# Acionamentos_valvula.net
KiCad netlist of a schematic drawn in Altium Designer
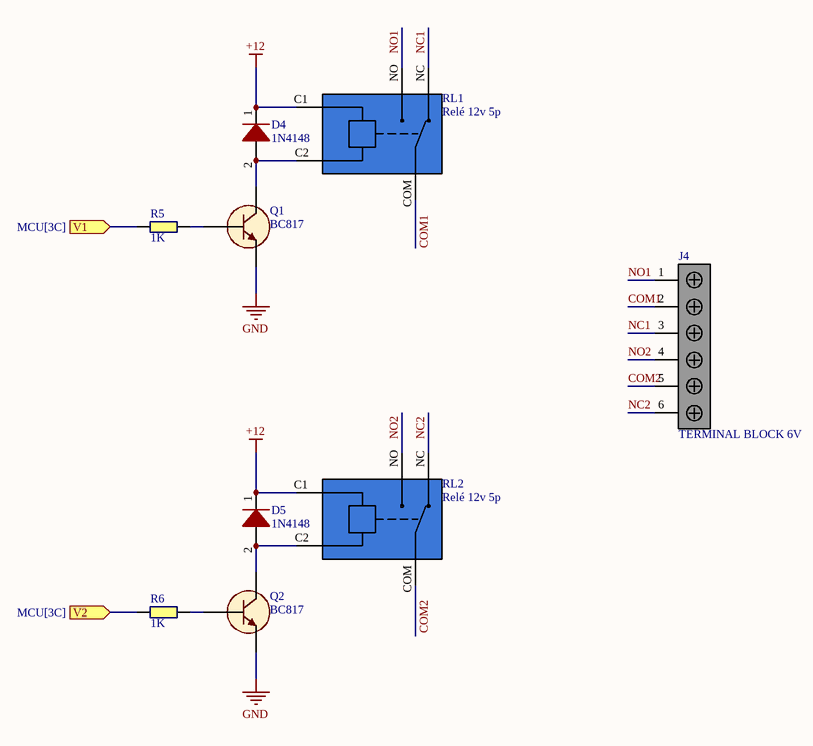
[diagram p0: Acionamentos valvula.SchDoc]

(export (version "E")
  (design (tool "Eeschema 10.0.6"))
  (components
    (comp (ref "D4")
      (value "1N4148")
      (footprint "DIOMELF3516N")
      (description "Diodo rapido")
      (fields (field (name "PUBLISHER") "Altium Limited"))
      (libsource (lib "Gerenciador de abastecimento") (part "DIODO 1N4148"))
    )
    (comp (ref "D5")
      (value "1N4148")
      (footprint "DIOMELF3516N")
      (description "Diodo rapido")
      (fields (field (name "PUBLISHER") "Altium Limited"))
      (libsource (lib "Gerenciador de abastecimento") (part "DIODO 1N4148"))
    )
    (comp (ref "J4")
      (value "TERMINAL BLOCK 6V")
      (footprint "Terminal block 5mm 6V")
      (description "Block, Terminal; 6 A; 63 V; 5 mm; 26 to 20 AWG; 6 Screw; Soldering; 1.5 kV")
      (libsource (lib "Gerenciador de abastecimento") (part "TERMINAL BLOCK 6V"))
    )
    (comp (ref "Q1")
      (value "BC817")
      (footprint "SOT23")
      (libsource (lib "Gerenciador de abastecimento") (part "BC817"))
    )
    (comp (ref "Q2")
      (value "BC817")
      (footprint "SOT23")
      (libsource (lib "Gerenciador de abastecimento") (part "BC817"))
    )
    (comp (ref "R5")
      (value "1K")
      (footprint "RESISTOR 1/4W 0805")
      (description "Resistor")
      (fields (field (name "PUBLISHER") "Altium Limited"))
      (libsource (lib "Gerenciador de abastecimento") (part "RESISTOR 1/4W"))
    )
    (comp (ref "R6")
      (value "1K")
      (footprint "RESISTOR 1/4W 0805")
      (description "Resistor")
      (fields (field (name "PUBLISHER") "Altium Limited"))
      (libsource (lib "Gerenciador de abastecimento") (part "RESISTOR 1/4W"))
    )
    (comp (ref "RL1")
      (value "Relé 12v 5p")
      (footprint "RELAY")
      (libsource (lib "Gerenciador de abastecimento") (part "Relé 12v 5p"))
    )
    (comp (ref "RL2")
      (value "Relé 12v 5p")
      (footprint "RELAY")
      (libsource (lib "Gerenciador de abastecimento") (part "Relé 12v 5p"))
    )
  )
  (nets
    (net (code "1") (name "+12") (class "Default")
      (node (ref "D4") (pin "1") (pinfunction "1_1") (pintype "passive"))
      (node (ref "D5") (pin "1") (pinfunction "1_1") (pintype "passive"))
      (node (ref "RL1") (pin "C1") (pinfunction "COIL_1_C1") (pintype "passive"))
      (node (ref "RL2") (pin "C1") (pinfunction "COIL_1_C1") (pintype "passive"))
    )
    (net (code "2") (name "/COM1") (class "Default")
      (node (ref "J4") (pin "2") (pinfunction "2_2") (pintype "passive"))
      (node (ref "RL1") (pin "COM") (pinfunction "COM_COM") (pintype "passive"))
    )
    (net (code "3") (name "/COM2") (class "Default")
      (node (ref "J4") (pin "5") (pinfunction "5_5") (pintype "passive"))
      (node (ref "RL2") (pin "COM") (pinfunction "COM_COM") (pintype "passive"))
    )
    (net (code "4") (name "/NC1") (class "Default")
      (node (ref "J4") (pin "3") (pinfunction "3_3") (pintype "passive"))
      (node (ref "RL1") (pin "NC") (pinfunction "NC_NC") (pintype "passive"))
    )
    (net (code "5") (name "/NC2") (class "Default")
      (node (ref "J4") (pin "6") (pinfunction "6_6") (pintype "passive"))
      (node (ref "RL2") (pin "NC") (pinfunction "NC_NC") (pintype "passive"))
    )
    (net (code "6") (name "/NO1") (class "Default")
      (node (ref "J4") (pin "1") (pinfunction "1_1") (pintype "passive"))
      (node (ref "RL1") (pin "NO") (pinfunction "NO_NO") (pintype "passive"))
    )
    (net (code "7") (name "/NO2") (class "Default")
      (node (ref "J4") (pin "4") (pinfunction "4_4") (pintype "passive"))
      (node (ref "RL2") (pin "NO") (pinfunction "NO_NO") (pintype "passive"))
    )
    (net (code "8") (name "/V1") (class "Default")
      (node (ref "R5") (pin "1") (pinfunction "1_1") (pintype "passive"))
    )
    (net (code "9") (name "/V2") (class "Default")
      (node (ref "R6") (pin "1") (pinfunction "1_1") (pintype "passive"))
    )
    (net (code "10") (name "GND") (class "Default")
      (node (ref "Q1") (pin "2") (pinfunction "E_2") (pintype "passive"))
      (node (ref "Q2") (pin "2") (pinfunction "E_2") (pintype "passive"))
    )
    (net (code "11") (name "Net-(Q1-B)") (class "Default")
      (node (ref "Q1") (pin "1") (pinfunction "B_1") (pintype "passive"))
      (node (ref "R5") (pin "2") (pinfunction "2_2") (pintype "passive"))
    )
    (net (code "12") (name "Net-(Q1-C)") (class "Default")
      (node (ref "D4") (pin "2") (pinfunction "2_2") (pintype "passive"))
      (node (ref "Q1") (pin "3") (pinfunction "C_3") (pintype "passive"))
      (node (ref "RL1") (pin "C2") (pinfunction "COIL_2_C2") (pintype "passive"))
    )
    (net (code "13") (name "Net-(Q2-B)") (class "Default")
      (node (ref "Q2") (pin "1") (pinfunction "B_1") (pintype "passive"))
      (node (ref "R6") (pin "2") (pinfunction "2_2") (pintype "passive"))
    )
    (net (code "14") (name "Net-(Q2-C)") (class "Default")
      (node (ref "D5") (pin "2") (pinfunction "2_2") (pintype "passive"))
      (node (ref "Q2") (pin "3") (pinfunction "C_3") (pintype "passive"))
      (node (ref "RL2") (pin "C2") (pinfunction "COIL_2_C2") (pintype "passive"))
    )
  )
)
